# ICS-43434.net
KiCad netlist of a schematic drawn in EAGLE
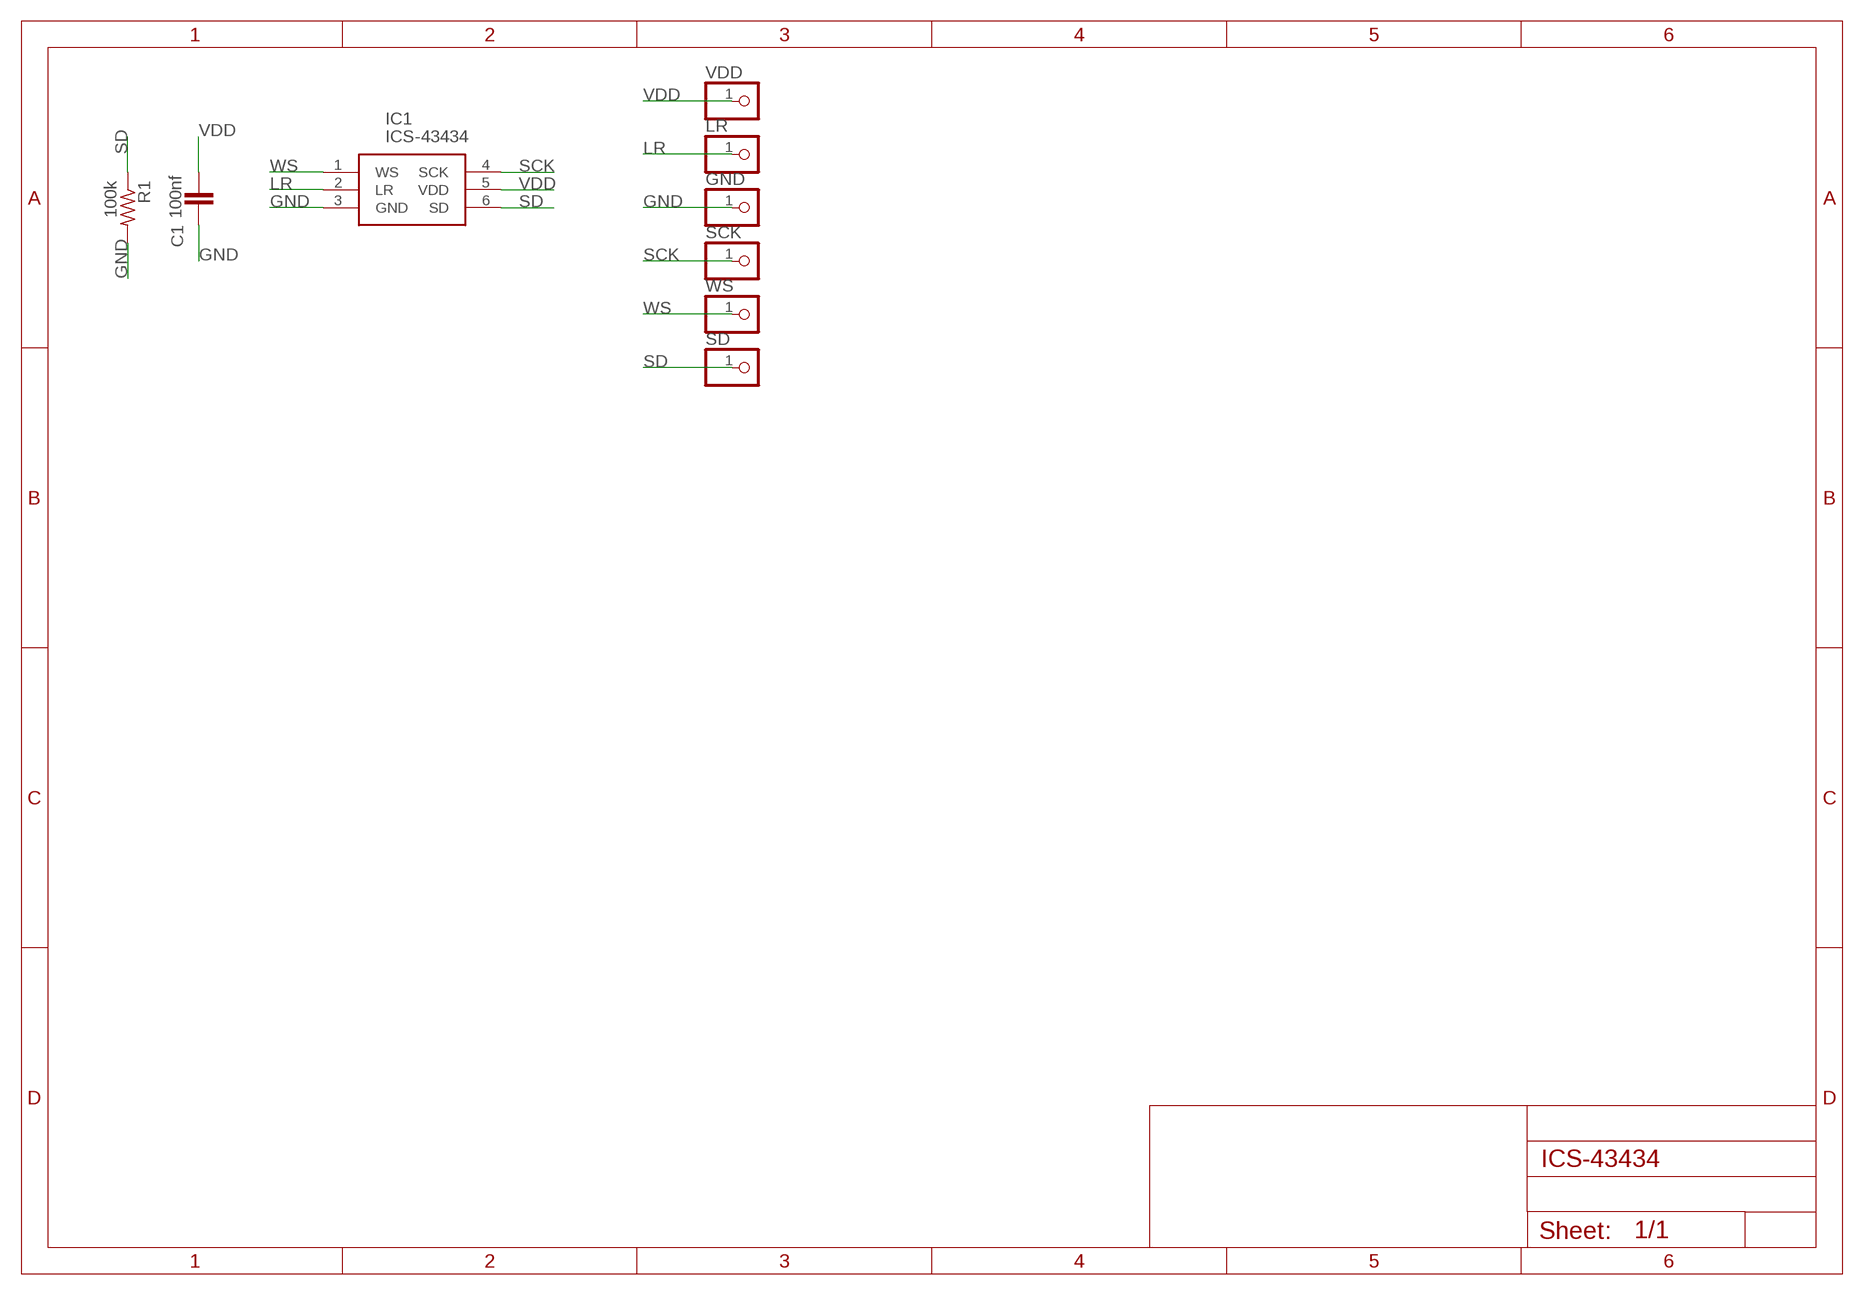
[diagram p0: schematic, sheet 1]

(export (version "E")
  (design (tool "Eeschema 10.0.6"))
  (components
    (comp (ref "C1")
      (value "100nf")
      (footprint "eagle-import:CAP_0805")
      (fields
        (field (name "DIGIKEY_PART_NUMBER") "311-1140-2-ND")
        (field (name "MANUFACTURER") "Yageo")
        (field (name "MPN") "CC0805KRX7R9BB104")
        (field (name "CREATED_BY") "PCBLayout.com")
      )
      (libsource (lib "eagle-import") (part "CC0805KRX7R9BB104"))
    )
    (comp (ref "GND")
      (value "PINHD-1X1CB")
      (footprint "eagle-import:1X01-CLEANBIG")
      (libsource (lib "eagle-import") (part "PINHD-1X1CB"))
    )
    (comp (ref "IC1")
      (value "ICS-43434")
      (footprint "eagle-import:ICS43434")
      (fields (field (name "MOUSER_PART_NUMBER") "410-ICS-43434"))
      (libsource (lib "eagle-import") (part "ICS-43434"))
    )
    (comp (ref "LR")
      (value "PINHD-1X1CB")
      (footprint "eagle-import:1X01-CLEANBIG")
      (libsource (lib "eagle-import") (part "PINHD-1X1CB"))
    )
    (comp (ref "R1")
      (value "100k")
      (footprint "eagle-import:R0805")
      (libsource (lib "eagle-import") (part "R-US_R0805"))
    )
    (comp (ref "SCK")
      (value "PINHD-1X1CB")
      (footprint "eagle-import:1X01-CLEANBIG")
      (libsource (lib "eagle-import") (part "PINHD-1X1CB"))
    )
    (comp (ref "SD")
      (value "PINHD-1X1CB")
      (footprint "eagle-import:1X01-CLEANBIG")
      (libsource (lib "eagle-import") (part "PINHD-1X1CB"))
    )
    (comp (ref "VDD")
      (value "PINHD-1X1CB")
      (footprint "eagle-import:1X01-CLEANBIG")
      (libsource (lib "eagle-import") (part "PINHD-1X1CB"))
    )
    (comp (ref "WS")
      (value "PINHD-1X1CB")
      (footprint "eagle-import:1X01-CLEANBIG")
      (libsource (lib "eagle-import") (part "PINHD-1X1CB"))
    )
  )
  (nets
    (net (code "1") (name "/GND") (class "Default")
      (node (ref "C1") (pin "1") (pinfunction "1_1") (pintype "passive"))
      (node (ref "GND") (pin "1") (pinfunction "1_1") (pintype "passive"))
      (node (ref "IC1") (pin "3") (pinfunction "GND_3") (pintype "bidirectional"))
      (node (ref "R1") (pin "2") (pinfunction "2_2") (pintype "passive"))
    )
    (net (code "2") (name "/LR") (class "Default")
      (node (ref "IC1") (pin "2") (pinfunction "LR_2") (pintype "bidirectional"))
      (node (ref "LR") (pin "1") (pinfunction "1_1") (pintype "passive"))
    )
    (net (code "3") (name "/SCK") (class "Default")
      (node (ref "IC1") (pin "4") (pinfunction "SCK_4") (pintype "bidirectional"))
      (node (ref "SCK") (pin "1") (pinfunction "1_1") (pintype "passive"))
    )
    (net (code "4") (name "/SD") (class "Default")
      (node (ref "IC1") (pin "6") (pinfunction "SD_6") (pintype "bidirectional"))
      (node (ref "R1") (pin "1") (pinfunction "1_1") (pintype "passive"))
      (node (ref "SD") (pin "1") (pinfunction "1_1") (pintype "passive"))
    )
    (net (code "5") (name "/VDD") (class "Default")
      (node (ref "C1") (pin "2") (pinfunction "2_2") (pintype "passive"))
      (node (ref "IC1") (pin "5") (pinfunction "VDD_5") (pintype "bidirectional"))
      (node (ref "VDD") (pin "1") (pinfunction "1_1") (pintype "passive"))
    )
    (net (code "6") (name "/WS") (class "Default")
      (node (ref "IC1") (pin "1") (pinfunction "WS_1") (pintype "bidirectional"))
      (node (ref "WS") (pin "1") (pinfunction "1_1") (pintype "passive"))
    )
  )
)
